# HeartRateBand.net
KiCad netlist of a schematic drawn in Altium Designer
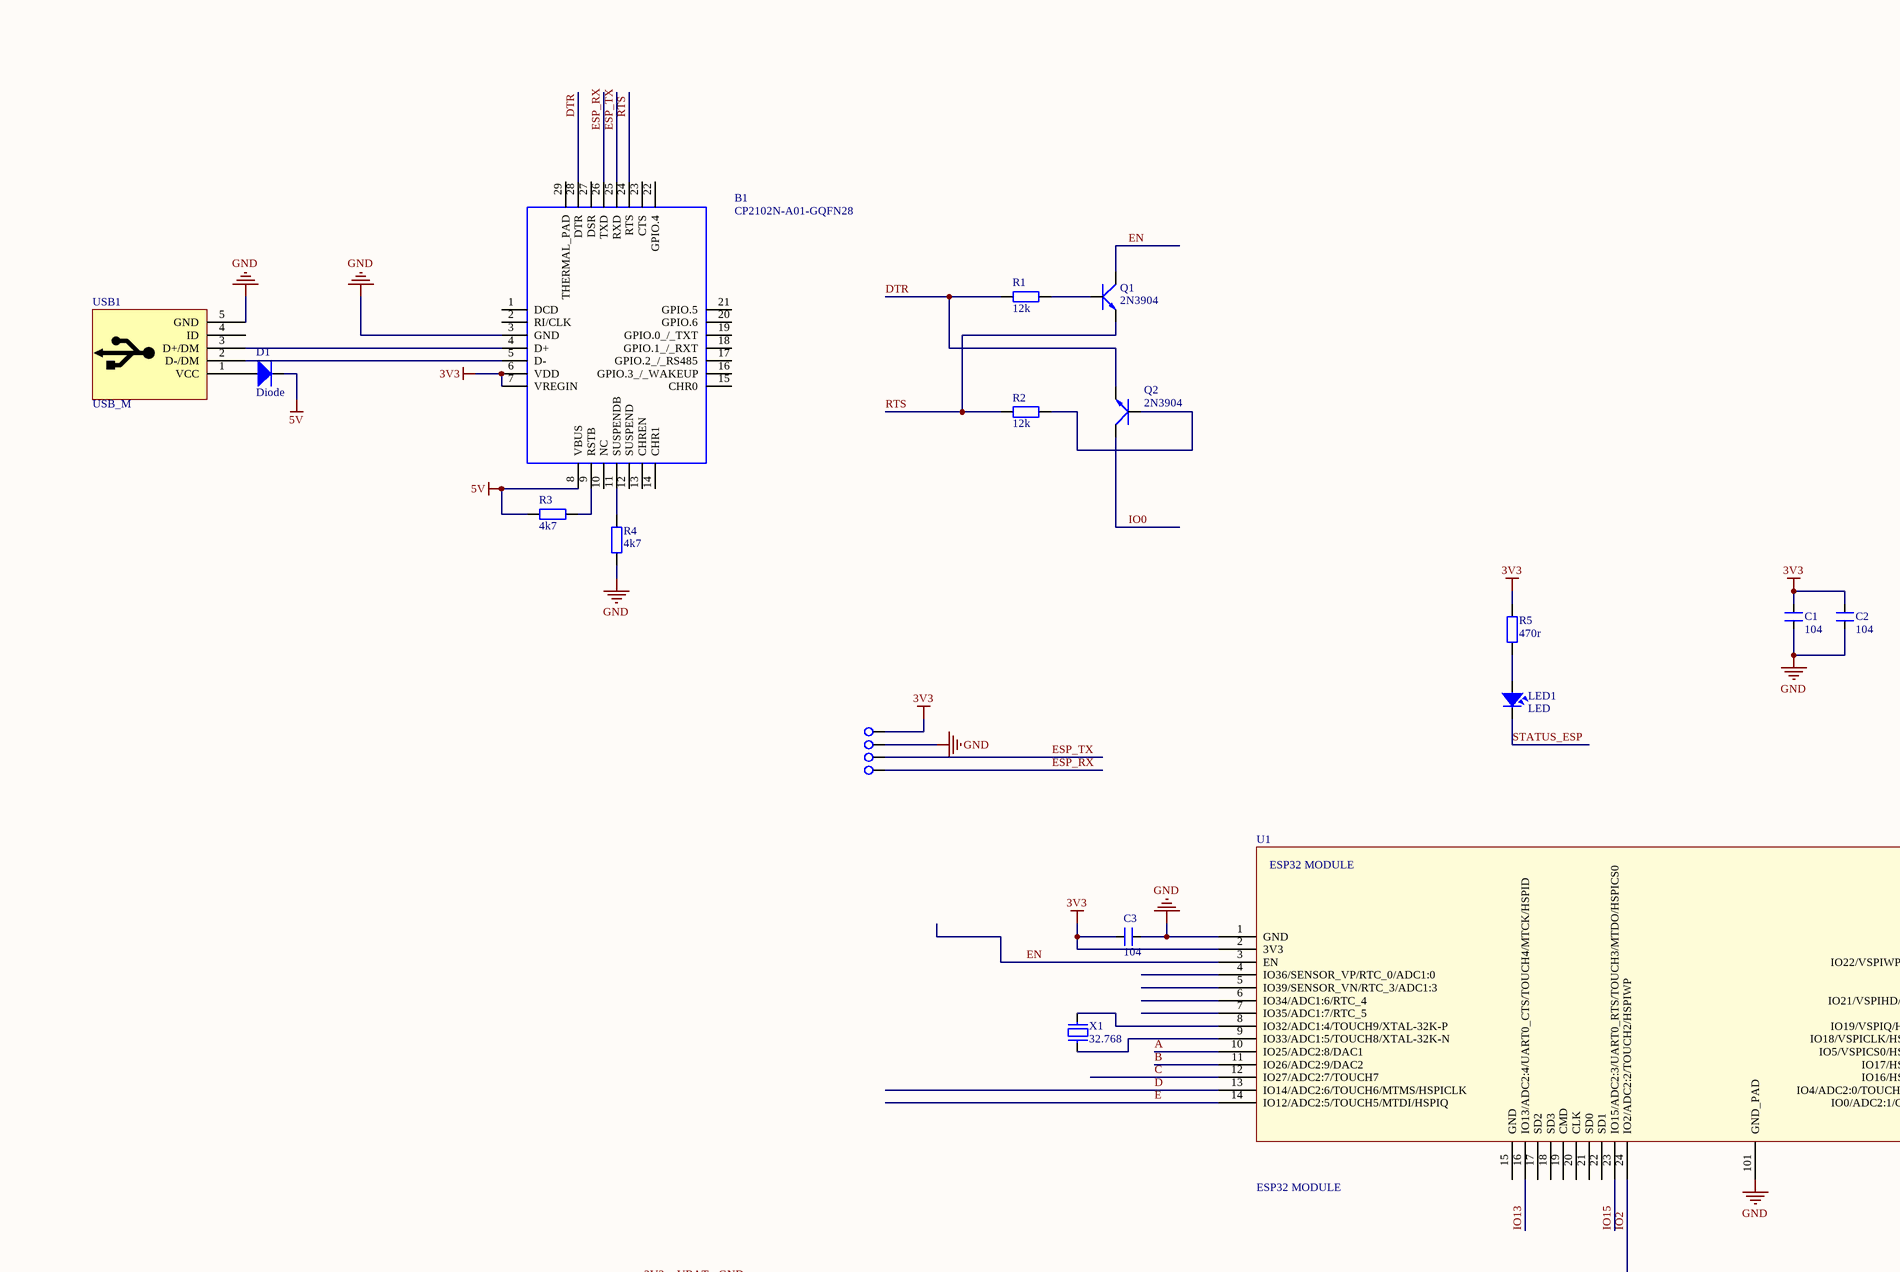
[diagram p0: HeartRateBand.SchDoc, top left]
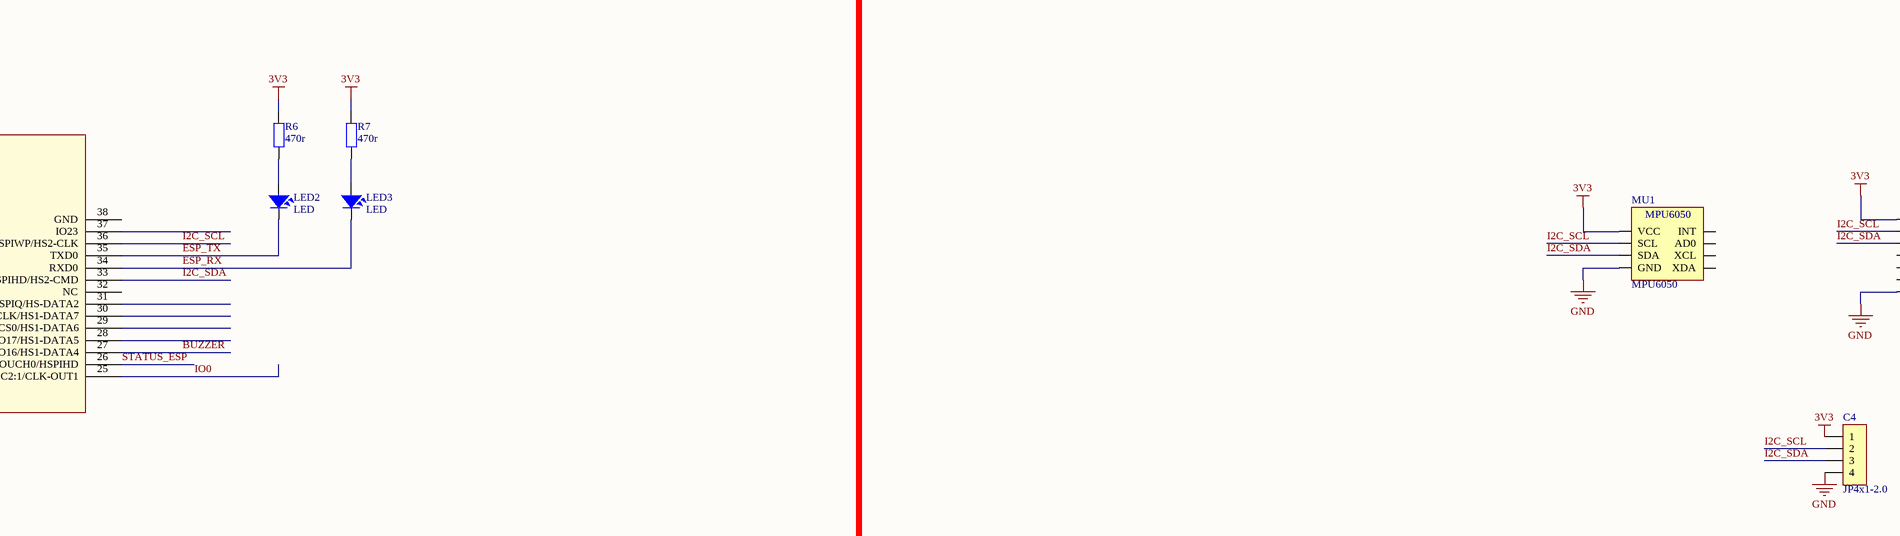
[diagram p1: HeartRateBand.SchDoc, top middle]
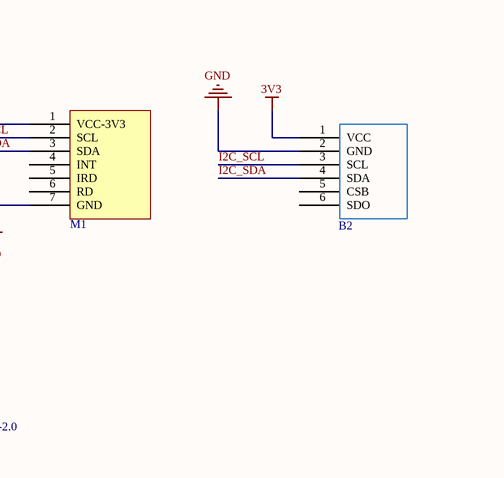
[diagram p2: HeartRateBand.SchDoc, top right]
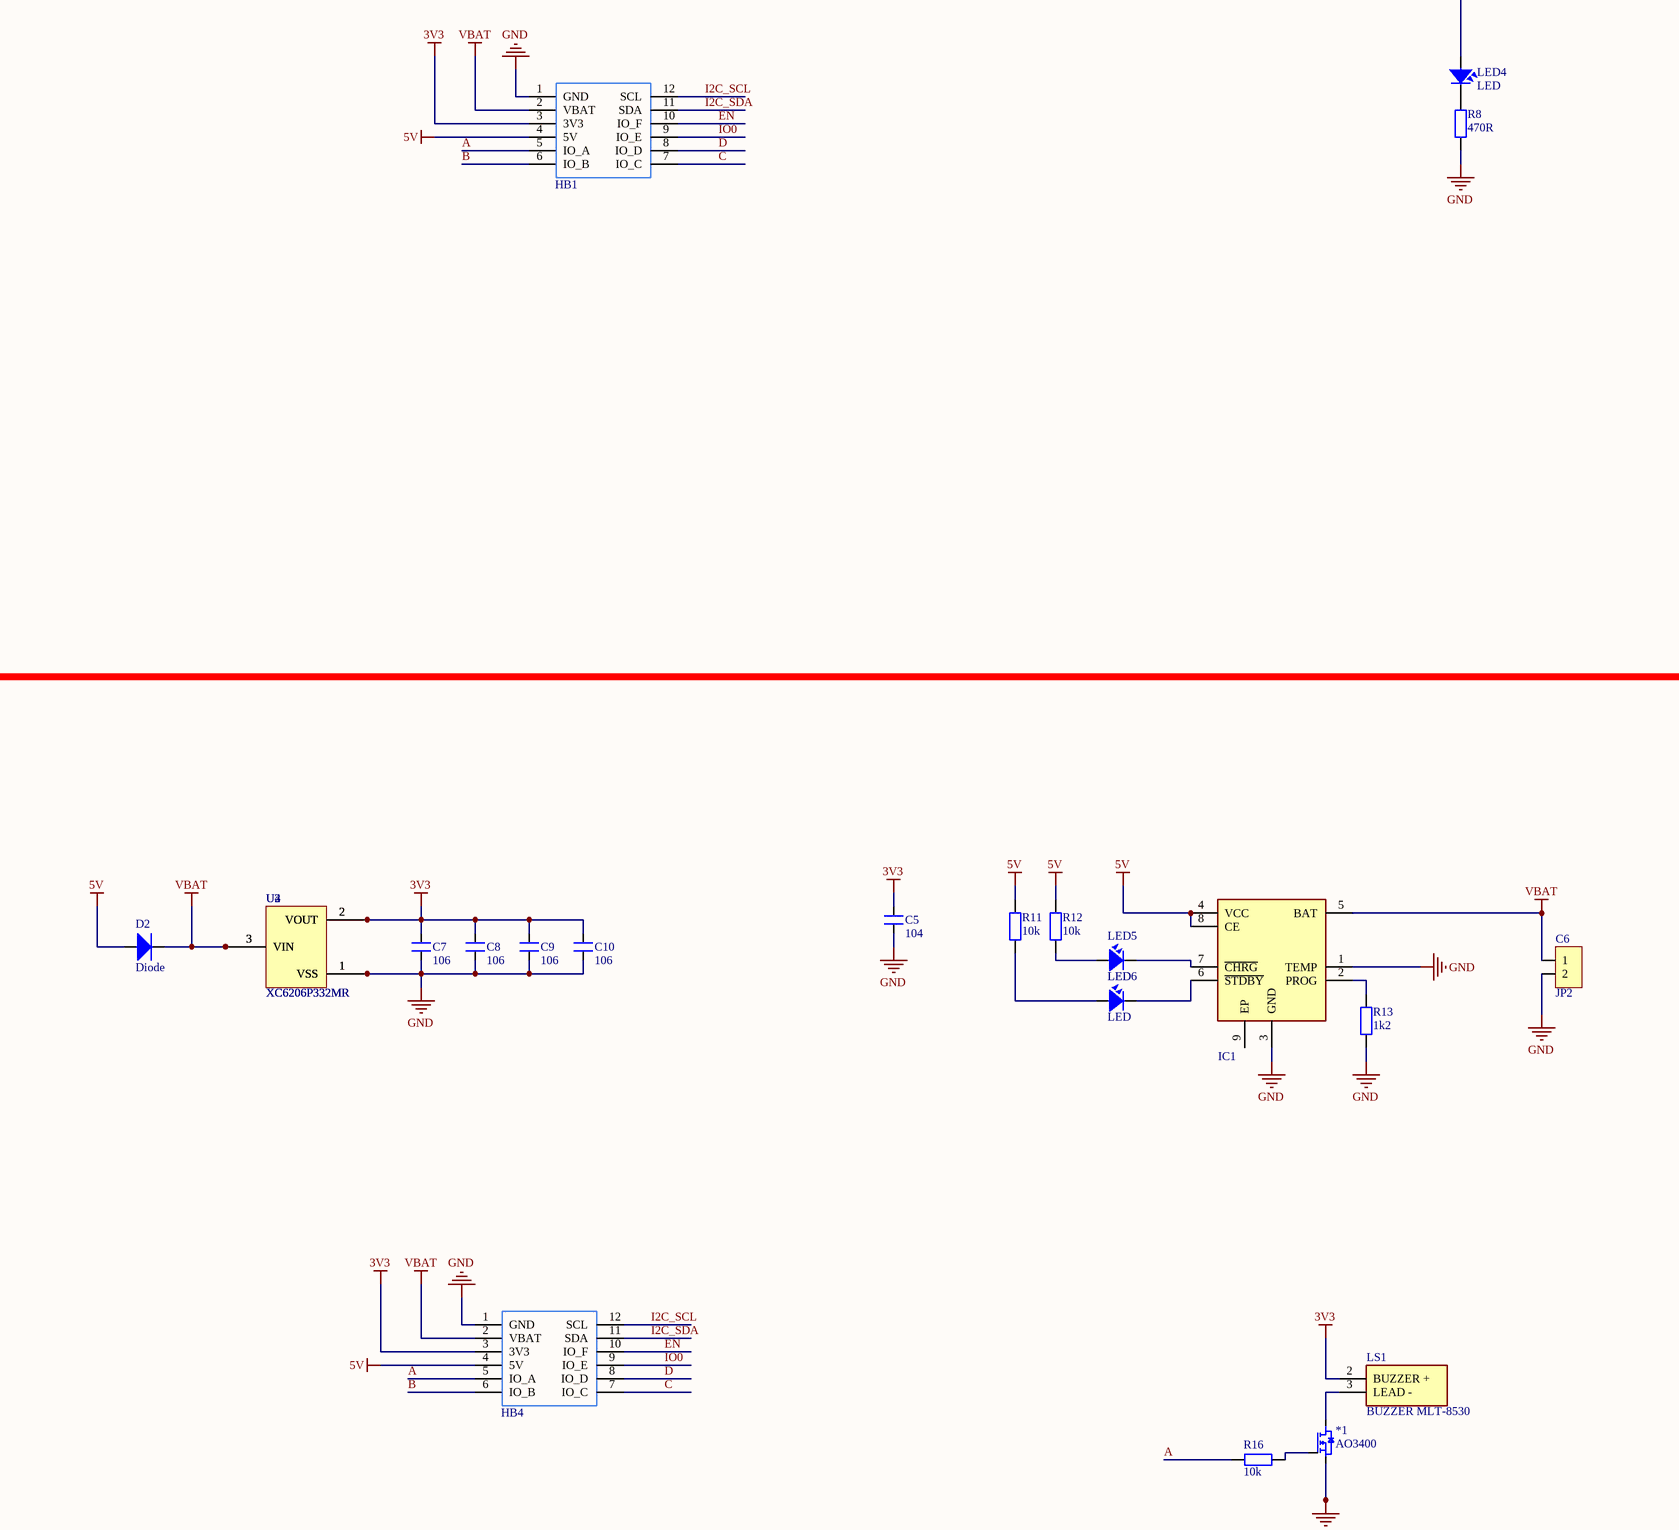
[diagram p3: HeartRateBand.SchDoc, centre left]
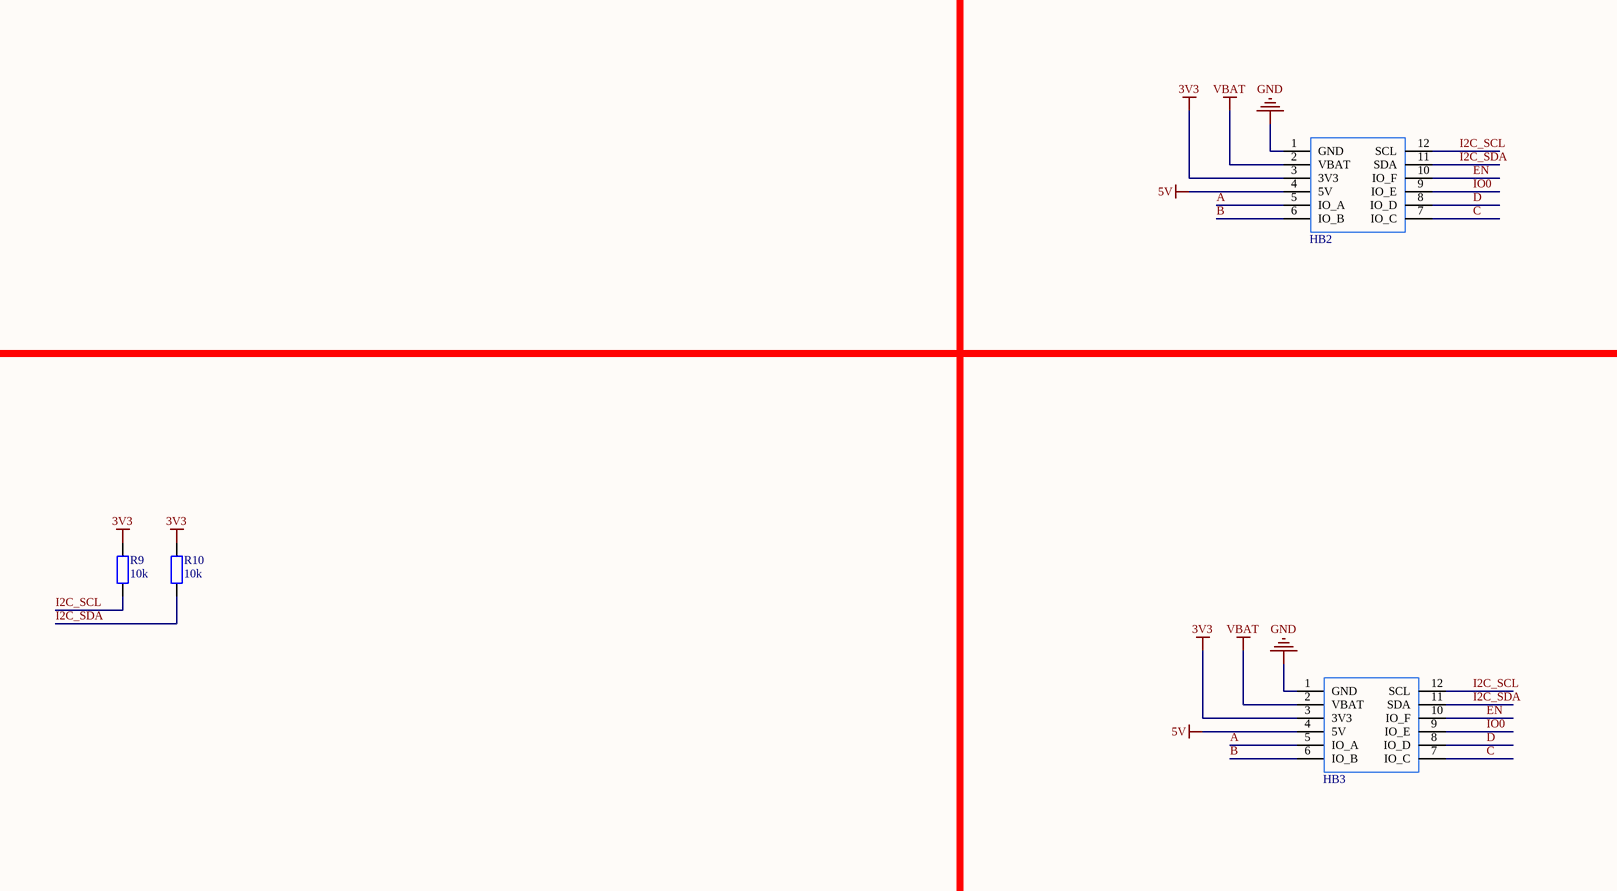
[diagram p4: HeartRateBand.SchDoc, centre middle]
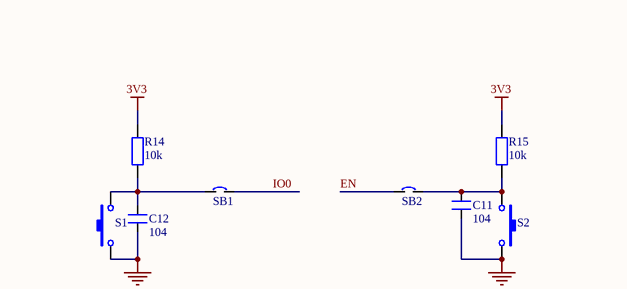
[diagram p5: HeartRateBand.SchDoc, centre right]
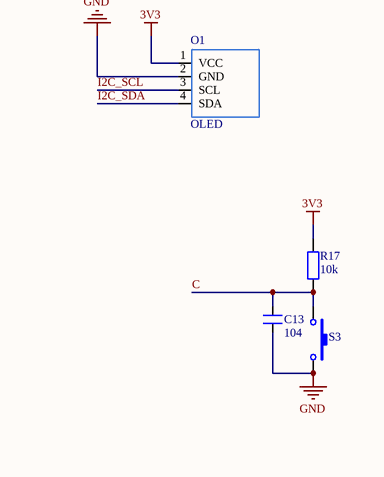
[diagram p6: HeartRateBand.SchDoc, bottom middle]
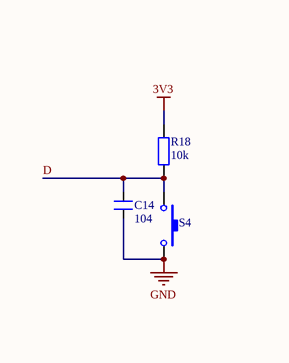
[diagram p7: HeartRateBand.SchDoc, bottom right]

(export (version "E")
  (design (tool "Eeschema 10.0.6"))
  (components
    (comp (ref "*1") (value "AO3400") (footprint "SOT23-123") (libsource (lib "OBIT_TESLA") (part "AO3400")))
    (comp (ref "*TP1") (value "TP") (footprint "TP") (libsource (lib "OBIT_TESLA") (part "TP")))
    (comp (ref "*TP2") (value "TP") (footprint "TP") (libsource (lib "OBIT_TESLA") (part "TP")))
    (comp (ref "*TP3") (value "TP") (footprint "TP") (libsource (lib "OBIT_TESLA") (part "TP")))
    (comp (ref "*TP4") (value "TP") (footprint "TP") (libsource (lib "OBIT_TESLA") (part "TP")))
    (comp (ref "B1")
      (value "CP2102N-A01-GQFN28")
      (footprint "QFN65P600X600X100-29N-D")
      (description "SILICON LABS - CP2102N-A01-GQFN28 - USB-UART INTERFACE BRIDGE, QFN-28")
      (libsource (lib "OBIT_TESLA") (part "CP2102N-A01-GQFN28"))
    )
    (comp (ref "B2")
      (value "BMP280")
      (footprint "BMP280")
      (description "https://iotmaker.vn/cam-bien-ap-suat-bmp280.html")
      (libsource (lib "OBIT_TESLA") (part "BMP280"))
    )
    (comp (ref "C1")
      (value "104")
      (footprint "SM-0603")
      (description "Cap SMD")
      (libsource (lib "OBIT_TESLA") (part "CM"))
    )
    (comp (ref "C2")
      (value "104")
      (footprint "SM-0603")
      (description "Cap SMD")
      (libsource (lib "OBIT_TESLA") (part "CM"))
    )
    (comp (ref "C3")
      (value "104")
      (footprint "SM-0603")
      (description "Cap SMD")
      (libsource (lib "OBIT_TESLA") (part "CM"))
    )
    (comp (ref "C4")
      (value "JP4x1-2.0")
      (footprint "J4-C1T")
      (description "WR-PHD 2.00 mm Socket Header")
      (fields
        (field (name "MANUFACTURER") "Würth Elektronik eiSos GmbH")
        (field (name "PARTNO") "62000411821")
        (field (name "CREATED BY") "Karrer Zheng")
      )
      (libsource (lib "OBIT_TESLA") (part "JP4x1-2.0"))
    )
    (comp (ref "C5")
      (value "104")
      (footprint "SM-0603")
      (description "Cap SMD")
      (libsource (lib "OBIT_TESLA") (part "CM"))
    )
    (comp (ref "C6")
      (value "JP2")
      (footprint "JP2-D1T")
      (description "WR-PHD 2.54 mm Angled Socket Header")
      (fields
        (field (name "MANUFACTURER") "Würth Elektronik eiSos GmbH")
        (field (name "PARTNO") "613002143121")
        (field (name "CREATED BY") "Karrer Zheng")
      )
      (libsource (lib "OBIT_TESLA") (part "JP2"))
    )
    (comp (ref "C7")
      (value "106")
      (footprint "SM-0603")
      (description "Cap SMD")
      (libsource (lib "OBIT_TESLA") (part "CM"))
    )
    (comp (ref "C8")
      (value "106")
      (footprint "SM-0603")
      (description "Cap SMD")
      (libsource (lib "OBIT_TESLA") (part "CM"))
    )
    (comp (ref "C9")
      (value "106")
      (footprint "SM-0603")
      (description "Cap SMD")
      (libsource (lib "OBIT_TESLA") (part "CM"))
    )
    (comp (ref "C10")
      (value "106")
      (footprint "SM-0603")
      (description "Cap SMD")
      (libsource (lib "OBIT_TESLA") (part "CM"))
    )
    (comp (ref "C11")
      (value "104")
      (footprint "SM-0603")
      (description "Cap SMD")
      (libsource (lib "OBIT_TESLA") (part "CM"))
    )
    (comp (ref "C12")
      (value "104")
      (footprint "SM-0603")
      (description "Cap SMD")
      (libsource (lib "OBIT_TESLA") (part "CM"))
    )
    (comp (ref "C13")
      (value "104")
      (footprint "SM-0603")
      (description "Cap SMD")
      (libsource (lib "OBIT_TESLA") (part "CM"))
    )
    (comp (ref "C14")
      (value "104")
      (footprint "SM-0603")
      (description "Cap SMD")
      (libsource (lib "OBIT_TESLA") (part "CM"))
    )
    (comp (ref "D1") (value "Diode") (footprint "DIO-SMD-123") (libsource (lib "OBIT_TESLA") (part "Diode")))
    (comp (ref "D2") (value "Diode") (footprint "DIO-SMD-106") (libsource (lib "OBIT_TESLA") (part "Diode")))
    (comp (ref "HB1")
      (value "HeartBand")
      (footprint "HeartBand")
      (libsource (lib "OBIT_TESLA") (part "HeartBand"))
    )
    (comp (ref "HB2")
      (value "HeartBand")
      (footprint "HeartBand")
      (libsource (lib "OBIT_TESLA") (part "HeartBand"))
    )
    (comp (ref "HB3")
      (value "HeartBand")
      (footprint "HeartBand")
      (libsource (lib "OBIT_TESLA") (part "HeartBand"))
    )
    (comp (ref "HB4")
      (value "HeartBand")
      (footprint "HeartBand")
      (libsource (lib "OBIT_TESLA") (part "HeartBand"))
    )
    (comp (ref "IC1")
      (value "TP4056-42-ESOP8")
      (footprint "SO-8")
      (description "Integrated Circuit")
      (libsource (lib "OBIT_TESLA") (part "TP4056-42-ESOP8"))
    )
    (comp (ref "LED1")
      (value "LED")
      (footprint "SM-LED-0805-Blue")
      (libsource (lib "OBIT_TESLA") (part "LED"))
    )
    (comp (ref "LED2")
      (value "LED")
      (footprint "SM-LED-0805-Blue")
      (libsource (lib "OBIT_TESLA") (part "LED"))
    )
    (comp (ref "LED3")
      (value "LED")
      (footprint "SM-LED-0805-Blue")
      (libsource (lib "OBIT_TESLA") (part "LED"))
    )
    (comp (ref "LED4")
      (value "LED")
      (footprint "SM-LED-0805-Blue")
      (libsource (lib "OBIT_TESLA") (part "LED"))
    )
    (comp (ref "LED5")
      (value "LED")
      (footprint "SM-LED-0805-Blue")
      (libsource (lib "OBIT_TESLA") (part "LED"))
    )
    (comp (ref "LED6")
      (value "LED")
      (footprint "SM-LED-0805-Blue")
      (libsource (lib "OBIT_TESLA") (part "LED"))
    )
    (comp (ref "LS1")
      (value "BUZZER MLT-8530")
      (footprint "MLT8530")
      (description "Loudspeaker or Buzzer")
      (fields (field (name "MANUFACTURER_PART_NUMBER") "MLT-8530"))
      (libsource (lib "OBIT_TESLA") (part "BUZZER MLT-8530"))
    )
    (comp (ref "M1")
      (value "Mã SP: 385470")
      (footprint "MAX30100")
      (libsource (lib "OBIT_TESLA") (part "MAX30100_HeartRateSensor"))
    )
    (comp (ref "MU1")
      (value "MPU6050")
      (footprint "MPU6050")
      (fields
        (field (name "MANUFACTURER") "Würth Elektronik eiSos GmbH")
        (field (name "PARTNO") "613004143121")
        (field (name "CREATED BY") "Karrer Zheng")
      )
      (libsource (lib "Tesla_Thinh") (part "MPU6050"))
    )
    (comp (ref "O1")
      (value "OLED")
      (footprint "OLED I2C MODULE")
      (libsource (lib "OBIT_TESLA") (part "OLED I2C MODULE"))
    )
    (comp (ref "Q1")
      (value "2N3904")
      (footprint "SOT23-231")
      (description "NPN 600mW, ECB")
      (libsource (lib "OBIT_TESLA") (part "2N3904"))
    )
    (comp (ref "Q2")
      (value "2N3904")
      (footprint "SOT23-231")
      (description "NPN 600mW, ECB")
      (libsource (lib "OBIT_TESLA") (part "2N3904"))
    )
    (comp (ref "R1")
      (value "12k")
      (footprint "RES-SMD-0603")
      (description "Resistor R1/4W")
      (libsource (lib "OBIT_TESLA") (part "R"))
    )
    (comp (ref "R2")
      (value "12k")
      (footprint "RES-SMD-0603")
      (description "Resistor R1/4W")
      (libsource (lib "OBIT_TESLA") (part "R"))
    )
    (comp (ref "R3")
      (value "4k7")
      (footprint "RES-SMD-0603")
      (description "Resistor R1/4W")
      (libsource (lib "OBIT_TESLA") (part "R"))
    )
    (comp (ref "R4")
      (value "4k7")
      (footprint "RES-SMD-0603")
      (description "Resistor R1/4W")
      (libsource (lib "OBIT_TESLA") (part "R"))
    )
    (comp (ref "R5")
      (value "470r")
      (footprint "RES-SMD-0603")
      (description "Resistor R1/4W")
      (libsource (lib "OBIT_TESLA") (part "R"))
    )
    (comp (ref "R6")
      (value "470r")
      (footprint "RES-SMD-0603")
      (description "Resistor R1/4W")
      (libsource (lib "OBIT_TESLA") (part "R"))
    )
    (comp (ref "R7")
      (value "470r")
      (footprint "RES-SMD-0603")
      (description "Resistor R1/4W")
      (libsource (lib "OBIT_TESLA") (part "R"))
    )
    (comp (ref "R8")
      (value "470R")
      (footprint "RES-SMD-0603")
      (description "Resistor R1/4W")
      (libsource (lib "OBIT_TESLA") (part "R"))
    )
    (comp (ref "R9")
      (value "10k")
      (footprint "RES-SMD-0603")
      (description "Resistor R1/4W")
      (libsource (lib "OBIT_TESLA") (part "R"))
    )
    (comp (ref "R10")
      (value "10k")
      (footprint "RES-SMD-0603")
      (description "Resistor R1/4W")
      (libsource (lib "OBIT_TESLA") (part "R"))
    )
    (comp (ref "R11")
      (value "10k")
      (footprint "RES-SMD-0603")
      (description "Resistor R1/4W")
      (libsource (lib "OBIT_TESLA") (part "R"))
    )
    (comp (ref "R12")
      (value "10k")
      (footprint "RES-SMD-0603")
      (description "Resistor R1/4W")
      (libsource (lib "OBIT_TESLA") (part "R"))
    )
    (comp (ref "R13")
      (value "1k2")
      (footprint "RES-SMD-0603")
      (description "Resistor R1/4W")
      (libsource (lib "OBIT_TESLA") (part "R"))
    )
    (comp (ref "R14")
      (value "10k")
      (footprint "RES-SMD-0603")
      (description "Resistor R1/4W")
      (libsource (lib "OBIT_TESLA") (part "R"))
    )
    (comp (ref "R15")
      (value "10k")
      (footprint "RES-SMD-0603")
      (description "Resistor R1/4W")
      (libsource (lib "OBIT_TESLA") (part "R"))
    )
    (comp (ref "R16")
      (value "10k")
      (footprint "RES-SMD-0603")
      (description "Resistor R1/4W")
      (libsource (lib "OBIT_TESLA") (part "R"))
    )
    (comp (ref "R17")
      (value "10k")
      (footprint "RES-SMD-0603")
      (description "Resistor R1/4W")
      (libsource (lib "OBIT_TESLA") (part "R"))
    )
    (comp (ref "R18")
      (value "10k")
      (footprint "RES-SMD-0603")
      (description "Resistor R1/4W")
      (libsource (lib "OBIT_TESLA") (part "R"))
    )
    (comp (ref "S1")
      (value "SW")
      (footprint "BUTTON-SMD 2PIN")
      (description "Switch-Button")
      (fields (field (name "PUBLISHER") "Altium Limited"))
      (libsource (lib "OBIT_TESLA") (part "SW-Button"))
    )
    (comp (ref "S2")
      (value "SW")
      (footprint "BUTTON-SMD 2PIN")
      (description "Switch-Button")
      (fields (field (name "PUBLISHER") "Altium Limited"))
      (libsource (lib "OBIT_TESLA") (part "SW-Button"))
    )
    (comp (ref "S3")
      (value "SW")
      (footprint "BUTTON-SMD 2PIN")
      (description "Switch-Button")
      (fields (field (name "PUBLISHER") "Altium Limited"))
      (libsource (lib "OBIT_TESLA") (part "SW-Button"))
    )
    (comp (ref "S4")
      (value "SW")
      (footprint "BUTTON-SMD 2PIN")
      (description "Switch-Button")
      (fields (field (name "PUBLISHER") "Altium Limited"))
      (libsource (lib "OBIT_TESLA") (part "SW-Button"))
    )
    (comp (ref "SB1") (value "SB") (footprint "SB") (libsource (lib "OBIT_TESLA") (part "SB")))
    (comp (ref "SB2") (value "SB") (footprint "SB") (libsource (lib "OBIT_TESLA") (part "SB")))
    (comp (ref "U1")
      (value "ESP32 MODULE")
      (footprint "ESP32S")
      (libsource (lib "OBIT_TESLA") (part "ESP32 MODULE"))
    )
    (comp (ref "U2")
      (value "XC6206P332MR")
      (footprint "SOT23-132")
      (description "3V3/0.5A")
      (libsource (lib "OBIT_TESLA") (part "XC6206P332MR"))
    )
    (comp (ref "U3")
      (value "XC6206P332MR")
      (footprint "SOT23-132")
      (description "3V3/0.5A")
      (libsource (lib "OBIT_TESLA") (part "XC6206P332MR"))
    )
    (comp (ref "U4")
      (value "XC6206P332MR")
      (footprint "SOT23-132")
      (description "3V3/0.5A")
      (libsource (lib "OBIT_TESLA") (part "XC6206P332MR"))
    )
    (comp (ref "USB1") (value "USB_M") (footprint "USB-M1") (libsource (lib "OBIT_TESLA") (part "USB_M")))
    (comp (ref "X1")
      (value "32.768")
      (footprint "XT32k")
      (description "Crystal, 32.768 KHz, -40 to 85 degC, 3.2 x 1.5 x 0.9 mm SMD")
      (libsource (lib "OBIT_TESLA") (part "XT2"))
    )
  )
  (nets
    (net (code "1") (name "/A") (class "Default")
      (node (ref "HB1") (pin "5") (pinfunction "IO_A_5") (pintype "passive"))
      (node (ref "HB2") (pin "5") (pinfunction "IO_A_5") (pintype "passive"))
      (node (ref "HB3") (pin "5") (pinfunction "IO_A_5") (pintype "passive"))
      (node (ref "HB4") (pin "5") (pinfunction "IO_A_5") (pintype "passive"))
      (node (ref "R16") (pin "2") (pinfunction "2_2") (pintype "passive"))
      (node (ref "U1") (pin "10") (pinfunction "IO25/ADC2:8/DAC1_10") (pintype "passive"))
    )
    (net (code "2") (name "/B") (class "Default")
      (node (ref "HB1") (pin "6") (pinfunction "IO_B_6") (pintype "passive"))
      (node (ref "HB2") (pin "6") (pinfunction "IO_B_6") (pintype "passive"))
      (node (ref "HB3") (pin "6") (pinfunction "IO_B_6") (pintype "passive"))
      (node (ref "HB4") (pin "6") (pinfunction "IO_B_6") (pintype "passive"))
      (node (ref "U1") (pin "11") (pinfunction "IO26/ADC2:9/DAC2_11") (pintype "passive"))
    )
    (net (code "3") (name "/BUZZER") (class "Default")
      (node (ref "U1") (pin "27") (pinfunction "IO16/HS1-DATA4_27") (pintype "passive"))
    )
    (net (code "4") (name "/C") (class "Default")
      (node (ref "C13") (pin "2") (pinfunction "2_2") (pintype "passive"))
      (node (ref "HB1") (pin "7") (pinfunction "IO_C_7") (pintype "passive"))
      (node (ref "HB2") (pin "7") (pinfunction "IO_C_7") (pintype "passive"))
      (node (ref "HB3") (pin "7") (pinfunction "IO_C_7") (pintype "passive"))
      (node (ref "HB4") (pin "7") (pinfunction "IO_C_7") (pintype "passive"))
      (node (ref "R17") (pin "2") (pinfunction "2_2") (pintype "passive"))
      (node (ref "S3") (pin "1") (pinfunction "1_1") (pintype "passive"))
      (node (ref "U1") (pin "12") (pinfunction "IO27/ADC2:7/TOUCH7_12") (pintype "passive"))
    )
    (net (code "5") (name "/D") (class "Default")
      (node (ref "C14") (pin "2") (pinfunction "2_2") (pintype "passive"))
      (node (ref "HB1") (pin "8") (pinfunction "IO_D_8") (pintype "passive"))
      (node (ref "HB2") (pin "8") (pinfunction "IO_D_8") (pintype "passive"))
      (node (ref "HB3") (pin "8") (pinfunction "IO_D_8") (pintype "passive"))
      (node (ref "HB4") (pin "8") (pinfunction "IO_D_8") (pintype "passive"))
      (node (ref "R18") (pin "2") (pinfunction "2_2") (pintype "passive"))
      (node (ref "S4") (pin "1") (pinfunction "1_1") (pintype "passive"))
      (node (ref "U1") (pin "13") (pinfunction "IO14/ADC2:6/TOUCH6/MTMS/HSPICLK_13") (pintype "passive"))
    )
    (net (code "6") (name "/DTR") (class "Default")
      (node (ref "B1") (pin "28") (pinfunction "DTR_28") (pintype "passive"))
      (node (ref "Q2") (pin "1") (pinfunction "E_1") (pintype "passive"))
      (node (ref "R1") (pin "2") (pinfunction "2_2") (pintype "passive"))
    )
    (net (code "7") (name "/E") (class "Default")
      (node (ref "U1") (pin "14") (pinfunction "IO12/ADC2:5/TOUCH5/MTDI/HSPIQ_14") (pintype "passive"))
    )
    (net (code "8") (name "/EN") (class "Default")
      (node (ref "HB1") (pin "10") (pinfunction "IO_F_10") (pintype "passive"))
      (node (ref "HB2") (pin "10") (pinfunction "IO_F_10") (pintype "passive"))
      (node (ref "HB3") (pin "10") (pinfunction "IO_F_10") (pintype "passive"))
      (node (ref "HB4") (pin "10") (pinfunction "IO_F_10") (pintype "passive"))
      (node (ref "Q1") (pin "3") (pinfunction "C_3") (pintype "passive"))
      (node (ref "SB2") (pin "1") (pintype "passive"))
      (node (ref "U1") (pin "3") (pinfunction "EN_3") (pintype "power_in"))
    )
    (net (code "9") (name "/ESP_RX") (class "Default")
      (node (ref "*TP4") (pin "1") (pintype "passive"))
      (node (ref "B1") (pin "26") (pinfunction "TXD_26") (pintype "passive"))
      (node (ref "LED3") (pin "2") (pinfunction "2_2") (pintype "passive"))
      (node (ref "U1") (pin "34") (pinfunction "RXD0_34") (pintype "passive"))
    )
    (net (code "10") (name "/ESP_TX") (class "Default")
      (node (ref "*TP3") (pin "1") (pintype "passive"))
      (node (ref "B1") (pin "25") (pinfunction "RXD_25") (pintype "passive"))
      (node (ref "LED2") (pin "2") (pinfunction "2_2") (pintype "passive"))
      (node (ref "U1") (pin "35") (pinfunction "TXD0_35") (pintype "passive"))
    )
    (net (code "11") (name "/I2C_SCL") (class "Default")
      (node (ref "B2") (pin "3") (pinfunction "SCL_3") (pintype "passive"))
      (node (ref "C4") (pin "2") (pinfunction "2_2") (pintype "passive"))
      (node (ref "HB1") (pin "12") (pinfunction "SCL_12") (pintype "passive"))
      (node (ref "HB2") (pin "12") (pinfunction "SCL_12") (pintype "passive"))
      (node (ref "HB3") (pin "12") (pinfunction "SCL_12") (pintype "passive"))
      (node (ref "HB4") (pin "12") (pinfunction "SCL_12") (pintype "passive"))
      (node (ref "M1") (pin "2") (pinfunction "SCL_2") (pintype "passive"))
      (node (ref "MU1") (pin "3") (pinfunction "SCL_3") (pintype "passive"))
      (node (ref "O1") (pin "3") (pinfunction "SCL_3") (pintype "passive"))
      (node (ref "R9") (pin "2") (pinfunction "2_2") (pintype "passive"))
      (node (ref "U1") (pin "36") (pinfunction "IO22/VSPIWP/HS2-CLK_36") (pintype "passive"))
    )
    (net (code "12") (name "/I2C_SDA") (class "Default")
      (node (ref "B2") (pin "4") (pinfunction "SDA_4") (pintype "passive"))
      (node (ref "C4") (pin "3") (pinfunction "3_3") (pintype "passive"))
      (node (ref "HB1") (pin "11") (pinfunction "SDA_11") (pintype "passive"))
      (node (ref "HB2") (pin "11") (pinfunction "SDA_11") (pintype "passive"))
      (node (ref "HB3") (pin "11") (pinfunction "SDA_11") (pintype "passive"))
      (node (ref "HB4") (pin "11") (pinfunction "SDA_11") (pintype "passive"))
      (node (ref "M1") (pin "3") (pinfunction "SDA_3") (pintype "passive"))
      (node (ref "MU1") (pin "4") (pinfunction "SDA_4") (pintype "passive"))
      (node (ref "O1") (pin "4") (pinfunction "SDA_4") (pintype "passive"))
      (node (ref "R10") (pin "2") (pinfunction "2_2") (pintype "passive"))
      (node (ref "U1") (pin "33") (pinfunction "IO21/VSPIHD/HS2-CMD_33") (pintype "passive"))
    )
    (net (code "13") (name "/IO0") (class "Default")
      (node (ref "HB1") (pin "9") (pinfunction "IO_E_9") (pintype "passive"))
      (node (ref "HB2") (pin "9") (pinfunction "IO_E_9") (pintype "passive"))
      (node (ref "HB3") (pin "9") (pinfunction "IO_E_9") (pintype "passive"))
      (node (ref "HB4") (pin "9") (pinfunction "IO_E_9") (pintype "passive"))
      (node (ref "Q2") (pin "3") (pinfunction "C_3") (pintype "passive"))
      (node (ref "SB1") (pin "2") (pintype "passive"))
      (node (ref "U1") (pin "25") (pinfunction "IO0/ADC2:1/CLK-OUT1_25") (pintype "passive"))
    )
    (net (code "14") (name "/IO2") (class "Default")
      (node (ref "LED4") (pin "1") (pinfunction "1_1") (pintype "passive"))
      (node (ref "U1") (pin "24") (pinfunction "IO2/ADC2:2/TOUCH2/HSPIWP_24") (pintype "passive"))
    )
    (net (code "15") (name "/IO13") (class "Default")
      (node (ref "U1") (pin "16") (pinfunction "IO13/ADC2:4/UART0_CTS/TOUCH4/MTCK/HSPID_16") (pintype "passive"))
    )
    (net (code "16") (name "/IO15") (class "Default")
      (node (ref "U1") (pin "23") (pinfunction "IO15/ADC2:3/UART0_RTS/TOUCH3/MTDO/HSPICS0_23") (pintype "passive"))
    )
    (net (code "17") (name "/RTS") (class "Default")
      (node (ref "B1") (pin "24") (pinfunction "RTS_24") (pintype "passive"))
      (node (ref "Q1") (pin "1") (pinfunction "E_1") (pintype "passive"))
      (node (ref "R2") (pin "2") (pinfunction "2_2") (pintype "passive"))
    )
    (net (code "18") (name "/STATUS_ESP") (class "Default")
      (node (ref "LED1") (pin "2") (pinfunction "2_2") (pintype "passive"))
      (node (ref "U1") (pin "26") (pinfunction "IO4/ADC2:0/TOUCH0/HSPIHD_26") (pintype "passive"))
    )
    (net (code "19") (name "3V3") (class "Default")
      (node (ref "*TP1") (pin "1") (pintype "passive"))
      (node (ref "B1") (pin "6") (pinfunction "VDD_6") (pintype "passive"))
      (node (ref "B1") (pin "7") (pinfunction "VREGIN_7") (pintype "passive"))
      (node (ref "B2") (pin "1") (pinfunction "VCC_1") (pintype "passive"))
      (node (ref "C1") (pin "2") (pinfunction "2_2") (pintype "passive"))
      (node (ref "C10") (pin "1") (pinfunction "1_1") (pintype "passive"))
      (node (ref "C2") (pin "2") (pinfunction "2_2") (pintype "passive"))
      (node (ref "C3") (pin "2") (pinfunction "2_2") (pintype "passive"))
      (node (ref "C4") (pin "1") (pinfunction "1_1") (pintype "passive"))
      (node (ref "C5") (pin "1") (pinfunction "1_1") (pintype "passive"))
      (node (ref "C7") (pin "1") (pinfunction "1_1") (pintype "passive"))
      (node (ref "C8") (pin "1") (pinfunction "1_1") (pintype "passive"))
      (node (ref "C9") (pin "1") (pinfunction "1_1") (pintype "passive"))
      (node (ref "HB1") (pin "3") (pinfunction "3V3_3") (pintype "passive"))
      (node (ref "HB2") (pin "3") (pinfunction "3V3_3") (pintype "passive"))
      (node (ref "HB3") (pin "3") (pinfunction "3V3_3") (pintype "passive"))
      (node (ref "HB4") (pin "3") (pinfunction "3V3_3") (pintype "passive"))
      (node (ref "LS1") (pin "2") (pinfunction "BUZZER_+_2") (pintype "passive"))
      (node (ref "M1") (pin "1") (pinfunction "VCC-3V3_1") (pintype "passive"))
      (node (ref "MU1") (pin "1") (pinfunction "VCC_1") (pintype "passive"))
      (node (ref "O1") (pin "1") (pinfunction "VCC_1") (pintype "passive"))
      (node (ref "R10") (pin "1") (pinfunction "1_1") (pintype "passive"))
      (node (ref "R14") (pin "2") (pinfunction "2_2") (pintype "passive"))
      (node (ref "R15") (pin "1") (pinfunction "1_1") (pintype "passive"))
      (node (ref "R17") (pin "1") (pinfunction "1_1") (pintype "passive"))
      (node (ref "R18") (pin "1") (pinfunction "1_1") (pintype "passive"))
      (node (ref "R5") (pin "2") (pinfunction "2_2") (pintype "passive"))
      (node (ref "R6") (pin "2") (pinfunction "2_2") (pintype "passive"))
      (node (ref "R7") (pin "2") (pinfunction "2_2") (pintype "passive"))
      (node (ref "R9") (pin "1") (pinfunction "1_1") (pintype "passive"))
      (node (ref "U1") (pin "2") (pinfunction "3V3_2") (pintype "power_in"))
      (node (ref "U2") (pin "2") (pinfunction "VOUT_2") (pintype "passive"))
      (node (ref "U3") (pin "2") (pinfunction "VOUT_2") (pintype "passive"))
      (node (ref "U4") (pin "2") (pinfunction "VOUT_2") (pintype "passive"))
    )
    (net (code "20") (name "5V") (class "Default")
      (node (ref "B1") (pin "8") (pinfunction "VBUS_8") (pintype "passive"))
      (node (ref "D1") (pin "2") (pinfunction "2_2") (pintype "passive"))
      (node (ref "D2") (pin "1") (pinfunction "1_1") (pintype "passive"))
      (node (ref "HB1") (pin "4") (pinfunction "5V_4") (pintype "passive"))
      (node (ref "HB2") (pin "4") (pinfunction "5V_4") (pintype "passive"))
      (node (ref "HB3") (pin "4") (pinfunction "5V_4") (pintype "passive"))
      (node (ref "HB4") (pin "4") (pinfunction "5V_4") (pintype "passive"))
      (node (ref "IC1") (pin "4") (pinfunction "VCC_4") (pintype "passive"))
      (node (ref "IC1") (pin "8") (pinfunction "CE_8") (pintype "passive"))
      (node (ref "R11") (pin "1") (pinfunction "1_1") (pintype "passive"))
      (node (ref "R12") (pin "1") (pinfunction "1_1") (pintype "passive"))
      (node (ref "R3") (pin "1") (pinfunction "1_1") (pintype "passive"))
    )
    (net (code "21") (name "GND") (class "Default")
      (node (ref "*1") (pin "3") (pintype "passive"))
      (node (ref "*TP2") (pin "1") (pintype "passive"))
      (node (ref "B1") (pin "3") (pinfunction "GND_3") (pintype "passive"))
      (node (ref "B2") (pin "2") (pinfunction "GND_2") (pintype "passive"))
      (node (ref "C1") (pin "1") (pinfunction "1_1") (pintype "passive"))
      (node (ref "C10") (pin "2") (pinfunction "2_2") (pintype "passive"))
      (node (ref "C11") (pin "1") (pinfunction "1_1") (pintype "passive"))
      (node (ref "C12") (pin "2") (pinfunction "2_2") (pintype "passive"))
      (node (ref "C13") (pin "1") (pinfunction "1_1") (pintype "passive"))
      (node (ref "C14") (pin "1") (pinfunction "1_1") (pintype "passive"))
      (node (ref "C2") (pin "1") (pinfunction "1_1") (pintype "passive"))
      (node (ref "C3") (pin "1") (pinfunction "1_1") (pintype "passive"))
      (node (ref "C4") (pin "4") (pinfunction "4_4") (pintype "passive"))
      (node (ref "C5") (pin "2") (pinfunction "2_2") (pintype "passive"))
      (node (ref "C6") (pin "2") (pinfunction "2_2") (pintype "passive"))
      (node (ref "C7") (pin "2") (pinfunction "2_2") (pintype "passive"))
      (node (ref "C8") (pin "2") (pinfunction "2_2") (pintype "passive"))
      (node (ref "C9") (pin "2") (pinfunction "2_2") (pintype "passive"))
      (node (ref "HB1") (pin "1") (pinfunction "GND_1") (pintype "passive"))
      (node (ref "HB2") (pin "1") (pinfunction "GND_1") (pintype "passive"))
      (node (ref "HB3") (pin "1") (pinfunction "GND_1") (pintype "passive"))
      (node (ref "HB4") (pin "1") (pinfunction "GND_1") (pintype "passive"))
      (node (ref "IC1") (pin "1") (pinfunction "TEMP_1") (pintype "passive"))
      (node (ref "IC1") (pin "3") (pinfunction "GND_3") (pintype "passive"))
      (node (ref "M1") (pin "7") (pinfunction "GND_7") (pintype "passive"))
      (node (ref "MU1") (pin "2") (pinfunction "GND_2") (pintype "passive"))
      (node (ref "O1") (pin "2") (pinfunction "GND_2") (pintype "passive"))
      (node (ref "R13") (pin "2") (pinfunction "2_2") (pintype "passive"))
      (node (ref "R4") (pin "1") (pinfunction "1_1") (pintype "passive"))
      (node (ref "R8") (pin "2") (pinfunction "2_2") (pintype "passive"))
      (node (ref "S1") (pin "1") (pinfunction "1_1") (pintype "passive"))
      (node (ref "S2") (pin "2") (pinfunction "2_2") (pintype "passive"))
      (node (ref "S3") (pin "2") (pinfunction "2_2") (pintype "passive"))
      (node (ref "S4") (pin "2") (pinfunction "2_2") (pintype "passive"))
      (node (ref "U1") (pin "1") (pinfunction "GND_1") (pintype "power_in"))
      (node (ref "U1") (pin "101") (pinfunction "GND_PAD_101") (pintype "power_in"))
      (node (ref "U2") (pin "1") (pinfunction "VSS_1") (pintype "passive"))
      (node (ref "U3") (pin "1") (pinfunction "VSS_1") (pintype "passive"))
      (node (ref "U4") (pin "1") (pinfunction "VSS_1") (pintype "passive"))
      (node (ref "USB1") (pin "5") (pinfunction "GND_5") (pintype "passive"))
    )
    (net (code "22") (name "Net-(*1-Pad1)") (class "Default")
      (node (ref "*1") (pin "1") (pintype "passive"))
      (node (ref "R16") (pin "1") (pinfunction "1_1") (pintype "passive"))
    )
    (net (code "23") (name "Net-(B1-D+)") (class "Default")
      (node (ref "B1") (pin "4") (pinfunction "D+_4") (pintype "passive"))
      (node (ref "USB1") (pin "3") (pinfunction "D+/DM_3") (pintype "passive"))
    )
    (net (code "24") (name "Net-(B1-D-)") (class "Default")
      (node (ref "B1") (pin "5") (pinfunction "D-_5") (pintype "passive"))
      (node (ref "USB1") (pin "2") (pinfunction "D-/DM_2") (pintype "passive"))
    )
    (net (code "25") (name "Net-(B1-RSTB)") (class "Default")
      (node (ref "B1") (pin "9") (pinfunction "RSTB_9") (pintype "passive"))
      (node (ref "R3") (pin "2") (pinfunction "2_2") (pintype "passive"))
    )
    (net (code "26") (name "Net-(B1-SUSPENDB)") (class "Default")
      (node (ref "B1") (pin "11") (pinfunction "SUSPENDB_11") (pintype "passive"))
      (node (ref "R4") (pin "2") (pinfunction "2_2") (pintype "passive"))
    )
    (net (code "27") (name "Net-(C11-Pad2)") (class "Default")
      (node (ref "C11") (pin "2") (pinfunction "2_2") (pintype "passive"))
      (node (ref "R15") (pin "2") (pinfunction "2_2") (pintype "passive"))
      (node (ref "S2") (pin "1") (pinfunction "1_1") (pintype "passive"))
      (node (ref "SB2") (pin "2") (pintype "passive"))
    )
    (net (code "28") (name "Net-(C12-Pad1)") (class "Default")
      (node (ref "C12") (pin "1") (pinfunction "1_1") (pintype "passive"))
      (node (ref "R14") (pin "1") (pinfunction "1_1") (pintype "passive"))
      (node (ref "S1") (pin "2") (pinfunction "2_2") (pintype "passive"))
      (node (ref "SB1") (pin "1") (pintype "passive"))
    )
    (net (code "29") (name "Net-(IC1-PROG)") (class "Default")
      (node (ref "IC1") (pin "2") (pinfunction "PROG_2") (pintype "passive"))
      (node (ref "R13") (pin "1") (pinfunction "1_1") (pintype "passive"))
    )
    (net (code "30") (name "Net-(IC1-~{CHRG})") (class "Default")
      (node (ref "IC1") (pin "7") (pinfunction "~{CHRG}_7") (pintype "passive"))
      (node (ref "LED5") (pin "2") (pinfunction "2_2") (pintype "passive"))
    )
    (net (code "31") (name "Net-(IC1-~{STDBY})") (class "Default")
      (node (ref "IC1") (pin "6") (pinfunction "~{STDBY}_6") (pintype "passive"))
      (node (ref "LED6") (pin "2") (pinfunction "2_2") (pintype "passive"))
    )
    (net (code "32") (name "Net-(LED1-Pad1)") (class "Default")
      (node (ref "LED1") (pin "1") (pinfunction "1_1") (pintype "passive"))
      (node (ref "R5") (pin "1") (pinfunction "1_1") (pintype "passive"))
    )
    (net (code "33") (name "Net-(LED2-Pad1)") (class "Default")
      (node (ref "LED2") (pin "1") (pinfunction "1_1") (pintype "passive"))
      (node (ref "R6") (pin "1") (pinfunction "1_1") (pintype "passive"))
    )
    (net (code "34") (name "Net-(LED3-Pad1)") (class "Default")
      (node (ref "LED3") (pin "1") (pinfunction "1_1") (pintype "passive"))
      (node (ref "R7") (pin "1") (pinfunction "1_1") (pintype "passive"))
    )
    (net (code "35") (name "Net-(LED4-Pad2)") (class "Default")
      (node (ref "LED4") (pin "2") (pinfunction "2_2") (pintype "passive"))
      (node (ref "R8") (pin "1") (pinfunction "1_1") (pintype "passive"))
    )
    (net (code "36") (name "Net-(LED5-Pad1)") (class "Default")
      (node (ref "LED5") (pin "1") (pinfunction "1_1") (pintype "passive"))
      (node (ref "R12") (pin "2") (pinfunction "2_2") (pintype "passive"))
    )
    (net (code "37") (name "Net-(LED6-Pad1)") (class "Default")
      (node (ref "LED6") (pin "1") (pinfunction "1_1") (pintype "passive"))
      (node (ref "R11") (pin "2") (pinfunction "2_2") (pintype "passive"))
    )
    (net (code "38") (name "Net-(LS1-LEAD_-)") (class "Default")
      (node (ref "*1") (pin "2") (pintype "passive"))
      (node (ref "LS1") (pin "3") (pinfunction "LEAD_-_3") (pintype "passive"))
    )
    (net (code "39") (name "Net-(Q1-B)") (class "Default")
      (node (ref "Q1") (pin "2") (pinfunction "B_2") (pintype "passive"))
      (node (ref "R1") (pin "1") (pinfunction "1_1") (pintype "passive"))
    )
    (net (code "40") (name "Net-(Q2-B)") (class "Default")
      (node (ref "Q2") (pin "2") (pinfunction "B_2") (pintype "passive"))
      (node (ref "R2") (pin "1") (pinfunction "1_1") (pintype "passive"))
    )
    (net (code "41") (name "Net-(U1-IO32{slash}ADC1:4{slash}TOUCH9{slash}XTAL-32K-P)") (class "Default")
      (node (ref "U1") (pin "8") (pinfunction "IO32/ADC1:4/TOUCH9/XTAL-32K-P_8") (pintype "passive"))
      (node (ref "X1") (pin "2") (pinfunction "2_2") (pintype "passive"))
    )
    (net (code "42") (name "Net-(U1-IO33{slash}ADC1:5{slash}TOUCH8{slash}XTAL-32K-N)") (class "Default")
      (node (ref "U1") (pin "9") (pinfunction "IO33/ADC1:5/TOUCH8/XTAL-32K-N_9") (pintype "passive"))
      (node (ref "X1") (pin "1") (pinfunction "1_1") (pintype "passive"))
    )
    (net (code "43") (name "Net-(USB1-VCC)") (class "Default")
      (node (ref "D1") (pin "1") (pinfunction "1_1") (pintype "passive"))
      (node (ref "USB1") (pin "1") (pinfunction "VCC_1") (pintype "passive"))
    )
    (net (code "44") (name "VBAT") (class "Default")
      (node (ref "C6") (pin "1") (pinfunction "1_1") (pintype "passive"))
      (node (ref "D2") (pin "2") (pinfunction "2_2") (pintype "passive"))
      (node (ref "HB1") (pin "2") (pinfunction "VBAT_2") (pintype "passive"))
      (node (ref "HB2") (pin "2") (pinfunction "VBAT_2") (pintype "passive"))
      (node (ref "HB3") (pin "2") (pinfunction "VBAT_2") (pintype "passive"))
      (node (ref "HB4") (pin "2") (pinfunction "VBAT_2") (pintype "passive"))
      (node (ref "IC1") (pin "5") (pinfunction "BAT_5") (pintype "passive"))
      (node (ref "U2") (pin "3") (pinfunction "VIN_3") (pintype "passive"))
      (node (ref "U3") (pin "3") (pinfunction "VIN_3") (pintype "passive"))
      (node (ref "U4") (pin "3") (pinfunction "VIN_3") (pintype "passive"))
    )
    (net (code "45") (name "unconnected-(B1-CHR0-Pad15)") (class "Default")
      (node (ref "B1") (pin "15") (pinfunction "CHR0_15") (pintype "passive"))
    )
    (net (code "46") (name "unconnected-(B1-CHR1-Pad14)") (class "Default")
      (node (ref "B1") (pin "14") (pinfunction "CHR1_14") (pintype "passive"))
    )
    (net (code "47") (name "unconnected-(B1-CHREN-Pad13)") (class "Default")
      (node (ref "B1") (pin "13") (pinfunction "CHREN_13") (pintype "passive"))
    )
    (net (code "48") (name "unconnected-(B1-CTS-Pad23)") (class "Default")
      (node (ref "B1") (pin "23") (pinfunction "CTS_23") (pintype "passive"))
    )
    (net (code "49") (name "unconnected-(B1-DCD-Pad1)") (class "Default")
      (node (ref "B1") (pin "1") (pinfunction "DCD_1") (pintype "passive"))
    )
    (net (code "50") (name "unconnected-(B1-DSR-Pad27)") (class "Default")
      (node (ref "B1") (pin "27") (pinfunction "DSR_27") (pintype "passive"))
    )
    (net (code "51") (name "unconnected-(B1-GPIO.0_{slash}_TXT-Pad19)") (class "Default")
      (node (ref "B1") (pin "19") (pinfunction "GPIO.0_/_TXT_19") (pintype "passive"))
    )
    (net (code "52") (name "unconnected-(B1-GPIO.1_{slash}_RXT-Pad18)") (class "Default")
      (node (ref "B1") (pin "18") (pinfunction "GPIO.1_/_RXT_18") (pintype "passive"))
    )
    (net (code "53") (name "unconnected-(B1-GPIO.2_{slash}_RS485-Pad17)") (class "Default")
      (node (ref "B1") (pin "17") (pinfunction "GPIO.2_/_RS485_17") (pintype "passive"))
    )
    (net (code "54") (name "unconnected-(B1-GPIO.3_{slash}_WAKEUP-Pad16)") (class "Default")
      (node (ref "B1") (pin "16") (pinfunction "GPIO.3_/_WAKEUP_16") (pintype "passive"))
    )
    (net (code "55") (name "unconnected-(B1-GPIO.4-Pad22)") (class "Default")
      (node (ref "B1") (pin "22") (pinfunction "GPIO.4_22") (pintype "passive"))
    )
    (net (code "56") (name "unconnected-(B1-GPIO.5-Pad21)") (class "Default")
      (node (ref "B1") (pin "21") (pinfunction "GPIO.5_21") (pintype "passive"))
    )
    (net (code "57") (name "unconnected-(B1-GPIO.6-Pad20)") (class "Default")
      (node (ref "B1") (pin "20") (pinfunction "GPIO.6_20") (pintype "passive"))
    )
    (net (code "58") (name "unconnected-(B1-NC-Pad10)") (class "Default")
      (node (ref "B1") (pin "10") (pinfunction "NC_10") (pintype "passive"))
    )
    (net (code "59") (name "unconnected-(B1-RI{slash}CLK-Pad2)") (class "Default")
      (node (ref "B1") (pin "2") (pinfunction "RI/CLK_2") (pintype "passive"))
    )
    (net (code "60") (name "unconnected-(B1-SUSPEND-Pad12)") (class "Default")
      (node (ref "B1") (pin "12") (pinfunction "SUSPEND_12") (pintype "passive"))
    )
    (net (code "61") (name "unconnected-(B1-THERMAL_PAD-Pad29)") (class "Default")
      (node (ref "B1") (pin "29") (pinfunction "THERMAL_PAD_29") (pintype "passive"))
    )
    (net (code "62") (name "unconnected-(B2-CSB-Pad5)") (class "Default")
      (node (ref "B2") (pin "5") (pinfunction "CSB_5") (pintype "passive"))
    )
    (net (code "63") (name "unconnected-(B2-SDO-Pad6)") (class "Default")
      (node (ref "B2") (pin "6") (pinfunction "SDO_6") (pintype "passive"))
    )
    (net (code "64") (name "unconnected-(IC1-EP-Pad9)") (class "Default")
      (node (ref "IC1") (pin "9") (pinfunction "EP_9") (pintype "passive"))
    )
    (net (code "65") (name "unconnected-(M1-INT-Pad4)") (class "Default")
      (node (ref "M1") (pin "4") (pinfunction "INT_4") (pintype "passive"))
    )
    (net (code "66") (name "unconnected-(M1-IRD-Pad5)") (class "Default")
      (node (ref "M1") (pin "5") (pinfunction "IRD_5") (pintype "passive"))
    )
    (net (code "67") (name "unconnected-(M1-RD-Pad6)") (class "Default")
      (node (ref "M1") (pin "6") (pinfunction "RD_6") (pintype "passive"))
    )
    (net (code "68") (name "unconnected-(MU1-AD0-Pad7)") (class "Default")
      (node (ref "MU1") (pin "7") (pinfunction "AD0_7") (pintype "passive"))
    )
    (net (code "69") (name "unconnected-(MU1-INT-Pad8)") (class "Default")
      (node (ref "MU1") (pin "8") (pinfunction "INT_8") (pintype "passive"))
    )
    (net (code "70") (name "unconnected-(MU1-XCL-Pad6)") (class "Default")
      (node (ref "MU1") (pin "6") (pinfunction "XCL_6") (pintype "passive"))
    )
    (net (code "71") (name "unconnected-(MU1-XDA-Pad5)") (class "Default")
      (node (ref "MU1") (pin "5") (pinfunction "XDA_5") (pintype "passive"))
    )
    (net (code "72") (name "unconnected-(U1-CLK-Pad20)") (class "Default")
      (node (ref "U1") (pin "20") (pinfunction "CLK_20") (pintype "passive"))
    )
    (net (code "73") (name "unconnected-(U1-CMD-Pad19)") (class "Default")
      (node (ref "U1") (pin "19") (pinfunction "CMD_19") (pintype "passive"))
    )
    (net (code "74") (name "unconnected-(U1-GND-Pad15)") (class "Default")
      (node (ref "U1") (pin "15") (pinfunction "GND_15") (pintype "power_in"))
    )
    (net (code "75") (name "unconnected-(U1-GND-Pad38)") (class "Default")
      (node (ref "U1") (pin "38") (pinfunction "GND_38") (pintype "power_in"))
    )
    (net (code "76") (name "unconnected-(U1-IO5{slash}VSPICS0{slash}HS1-DATA6-Pad29)") (class "Default")
      (node (ref "U1") (pin "29") (pinfunction "IO5/VSPICS0/HS1-DATA6_29") (pintype "passive"))
    )
    (net (code "77") (name "unconnected-(U1-IO17{slash}HS1-DATA5-Pad28)") (class "Default")
      (node (ref "U1") (pin "28") (pinfunction "IO17/HS1-DATA5_28") (pintype "passive"))
    )
    (net (code "78") (name "unconnected-(U1-IO18{slash}VSPICLK{slash}HS1-DATA7-Pad30)") (class "Default")
      (node (ref "U1") (pin "30") (pinfunction "IO18/VSPICLK/HS1-DATA7_30") (pintype "passive"))
    )
    (net (code "79") (name "unconnected-(U1-IO19{slash}VSPIQ{slash}HS-DATA2-Pad31)") (class "Default")
      (node (ref "U1") (pin "31") (pinfunction "IO19/VSPIQ/HS-DATA2_31") (pintype "passive"))
    )
    (net (code "80") (name "unconnected-(U1-IO23-Pad37)") (class "Default")
      (node (ref "U1") (pin "37") (pinfunction "IO23_37") (pintype "passive"))
    )
    (net (code "81") (name "unconnected-(U1-IO34{slash}ADC1:6{slash}RTC_4-Pad6)") (class "Default")
      (node (ref "U1") (pin "6") (pinfunction "IO34/ADC1:6/RTC_4_6") (pintype "passive"))
    )
    (net (code "82") (name "unconnected-(U1-IO35{slash}ADC1:7{slash}RTC_5-Pad7)") (class "Default")
      (node (ref "U1") (pin "7") (pinfunction "IO35/ADC1:7/RTC_5_7") (pintype "passive"))
    )
    (net (code "83") (name "unconnected-(U1-IO36{slash}SENSOR_VP{slash}RTC_0{slash}ADC1:0-Pad4)") (class "Default")
      (node (ref "U1") (pin "4") (pinfunction "IO36/SENSOR_VP/RTC_0/ADC1:0_4") (pintype "passive"))
    )
    (net (code "84") (name "unconnected-(U1-IO39{slash}SENSOR_VN{slash}RTC_3{slash}ADC1:3-Pad5)") (class "Default")
      (node (ref "U1") (pin "5") (pinfunction "IO39/SENSOR_VN/RTC_3/ADC1:3_5") (pintype "passive"))
    )
    (net (code "85") (name "unconnected-(U1-NC-Pad32)") (class "Default")
      (node (ref "U1") (pin "32") (pinfunction "NC_32") (pintype "passive"))
    )
    (net (code "86") (name "unconnected-(U1-SD0-Pad21)") (class "Default")
      (node (ref "U1") (pin "21") (pinfunction "SD0_21") (pintype "passive"))
    )
    (net (code "87") (name "unconnected-(U1-SD1-Pad22)") (class "Default")
      (node (ref "U1") (pin "22") (pinfunction "SD1_22") (pintype "passive"))
    )
    (net (code "88") (name "unconnected-(U1-SD2-Pad17)") (class "Default")
      (node (ref "U1") (pin "17") (pinfunction "SD2_17") (pintype "passive"))
    )
    (net (code "89") (name "unconnected-(U1-SD3-Pad18)") (class "Default")
      (node (ref "U1") (pin "18") (pinfunction "SD3_18") (pintype "passive"))
    )
    (net (code "90") (name "unconnected-(USB1-ID-Pad4)") (class "Default")
      (node (ref "USB1") (pin "4") (pinfunction "ID_4") (pintype "passive"))
    )
  )
)
